# Distro_schematic.net
KiCad netlist of a schematic drawn in Altium Designer
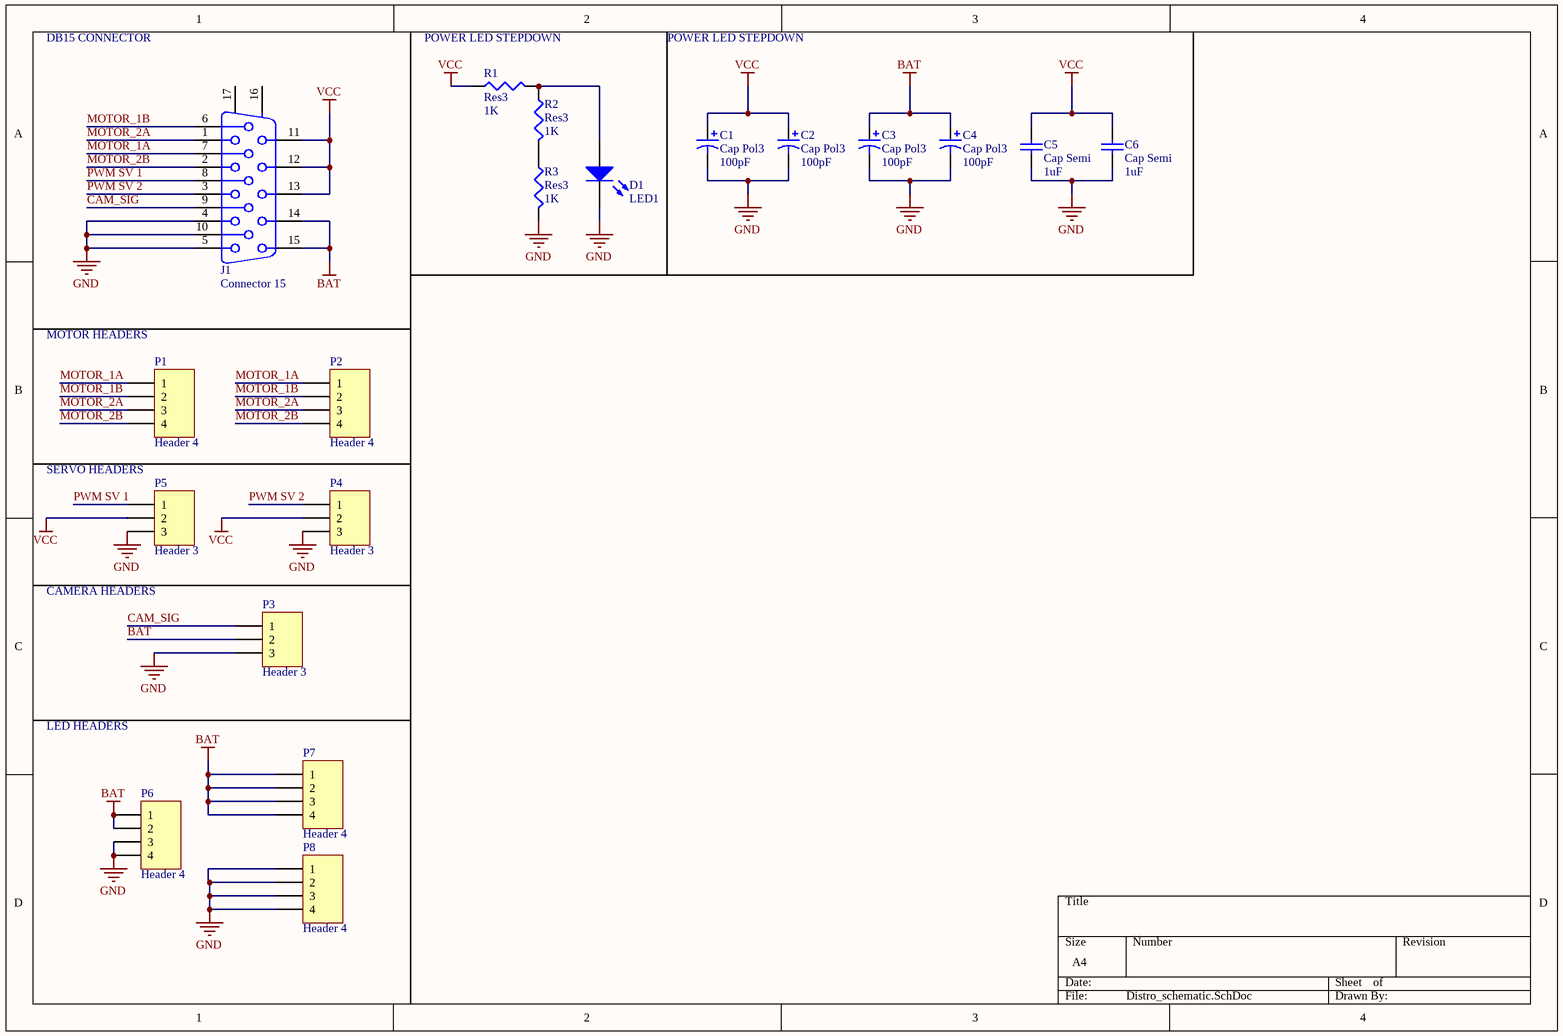
[diagram p0: Distro_schematic.SchDoc]

(export (version "E")
  (design (tool "Eeschema 10.0.6"))
  (components
    (comp (ref "C1")
      (value "Cap Pol3")
      (footprint "C0805")
      (description "Polarized Capacitor (Surface Mount)")
      (fields (field (name "ALTIUM_VALUE") "100pF") (field (name "PUBLISHER") "Altium Limited"))
      (libsource (lib "Miscellaneous Devices") (part "Cap Pol3"))
    )
    (comp (ref "C2")
      (value "Cap Pol3")
      (footprint "C0805")
      (description "Polarized Capacitor (Surface Mount)")
      (fields (field (name "ALTIUM_VALUE") "100pF") (field (name "PUBLISHER") "Altium Limited"))
      (libsource (lib "Miscellaneous Devices") (part "Cap Pol3"))
    )
    (comp (ref "C3")
      (value "Cap Pol3")
      (footprint "C0805")
      (description "Polarized Capacitor (Surface Mount)")
      (fields (field (name "ALTIUM_VALUE") "100pF") (field (name "PUBLISHER") "Altium Limited"))
      (libsource (lib "Miscellaneous Devices") (part "Cap Pol3"))
    )
    (comp (ref "C4")
      (value "Cap Pol3")
      (footprint "C0805")
      (description "Polarized Capacitor (Surface Mount)")
      (fields (field (name "ALTIUM_VALUE") "100pF") (field (name "PUBLISHER") "Altium Limited"))
      (libsource (lib "Miscellaneous Devices") (part "Cap Pol3"))
    )
    (comp (ref "C5")
      (value "Cap Semi")
      (footprint "C1206")
      (description "Capacitor (Semiconductor SIM Model)")
      (fields (field (name "ALTIUM_VALUE") "1uF") (field (name "PUBLISHER") "Altium Limited"))
      (libsource (lib "Miscellaneous Devices") (part "Cap Semi"))
    )
    (comp (ref "C6")
      (value "Cap Semi")
      (footprint "C1206")
      (description "Capacitor (Semiconductor SIM Model)")
      (fields (field (name "ALTIUM_VALUE") "1uF") (field (name "PUBLISHER") "Altium Limited"))
      (libsource (lib "Miscellaneous Devices") (part "Cap Semi"))
    )
    (comp (ref "D1")
      (value "LED1")
      (footprint "L0603")
      (description "Typical RED GaAs LED")
      (fields (field (name "PUBLISHER") "Altium Limited"))
      (libsource (lib "Miscellaneous Devices") (part "LED1"))
    )
    (comp (ref "J1")
      (value "Connector 15")
      (footprint "VGA_F:PCBComponent_1")
      (description "Receptacle Assembly, 15-Pin, Sim Line Connector")
      (fields (field (name "PUBLISHER") "Altium Limited"))
      (libsource (lib "Miscellaneous Connectors") (part "Connector 15"))
    )
    (comp (ref "P1")
      (value "Header 4")
      (footprint "HDR1X4")
      (description "Header, 4-Pin")
      (fields (field (name "PUBLISHER") "Altium Limited"))
      (libsource (lib "Miscellaneous Connectors") (part "Header 4"))
    )
    (comp (ref "P2")
      (value "Header 4")
      (footprint "HDR1X4")
      (description "Header, 4-Pin")
      (fields (field (name "PUBLISHER") "Altium Limited"))
      (libsource (lib "Miscellaneous Connectors") (part "Header 4"))
    )
    (comp (ref "P3")
      (value "Header 3")
      (footprint "HDR1X3")
      (description "Header, 3-Pin")
      (fields (field (name "PUBLISHER") "Altium Limited"))
      (libsource (lib "Miscellaneous Connectors") (part "Header 3"))
    )
    (comp (ref "P4")
      (value "Header 3")
      (footprint "HDR1X3")
      (description "Header, 3-Pin")
      (fields (field (name "PUBLISHER") "Altium Limited"))
      (libsource (lib "Miscellaneous Connectors") (part "Header 3"))
    )
    (comp (ref "P5")
      (value "Header 3")
      (footprint "HDR1X3")
      (description "Header, 3-Pin")
      (fields (field (name "PUBLISHER") "Altium Limited"))
      (libsource (lib "Miscellaneous Connectors") (part "Header 3"))
    )
    (comp (ref "P6")
      (value "Header 4")
      (footprint "HDR1X4")
      (description "Header, 4-Pin")
      (fields (field (name "PUBLISHER") "Altium Limited"))
      (libsource (lib "Miscellaneous Connectors") (part "Header 4"))
    )
    (comp (ref "P7")
      (value "Header 4")
      (footprint "HDR1X4")
      (description "Header, 4-Pin")
      (fields (field (name "PUBLISHER") "Altium Limited"))
      (libsource (lib "Miscellaneous Connectors") (part "Header 4"))
    )
    (comp (ref "P8")
      (value "Header 4")
      (footprint "HDR1X4")
      (description "Header, 4-Pin")
      (fields (field (name "PUBLISHER") "Altium Limited"))
      (libsource (lib "Miscellaneous Connectors") (part "Header 4"))
    )
    (comp (ref "R1")
      (value "Res3")
      (footprint "J1-0603")
      (description "Resistor")
      (fields (field (name "ALTIUM_VALUE") "1K") (field (name "PUBLISHER") "Altium Limited"))
      (libsource (lib "Miscellaneous Devices") (part "Res3"))
    )
    (comp (ref "R2")
      (value "Res3")
      (footprint "J1-0603")
      (description "Resistor")
      (fields (field (name "ALTIUM_VALUE") "1K") (field (name "PUBLISHER") "Altium Limited"))
      (libsource (lib "Miscellaneous Devices") (part "Res3"))
    )
    (comp (ref "R3")
      (value "Res3")
      (footprint "J1-0603")
      (description "Resistor")
      (fields (field (name "ALTIUM_VALUE") "1K") (field (name "PUBLISHER") "Altium Limited"))
      (libsource (lib "Miscellaneous Devices") (part "Res3"))
    )
  )
  (nets
    (net (code "1") (name "/CAM_SIG") (class "Default")
      (node (ref "J1") (pin "9") (pinfunction "9_9") (pintype "passive"))
      (node (ref "P3") (pin "1") (pinfunction "1_1") (pintype "passive"))
    )
    (net (code "2") (name "/MOTOR_1A") (class "Default")
      (node (ref "J1") (pin "7") (pinfunction "7_7") (pintype "passive"))
      (node (ref "P1") (pin "1") (pinfunction "1_1") (pintype "passive"))
      (node (ref "P2") (pin "1") (pinfunction "1_1") (pintype "passive"))
    )
    (net (code "3") (name "/MOTOR_1B") (class "Default")
      (node (ref "J1") (pin "6") (pinfunction "6_6") (pintype "passive"))
      (node (ref "P1") (pin "2") (pinfunction "2_2") (pintype "passive"))
      (node (ref "P2") (pin "2") (pinfunction "2_2") (pintype "passive"))
    )
    (net (code "4") (name "/MOTOR_2A") (class "Default")
      (node (ref "J1") (pin "1") (pinfunction "1_1") (pintype "passive"))
      (node (ref "P1") (pin "3") (pinfunction "3_3") (pintype "passive"))
      (node (ref "P2") (pin "3") (pinfunction "3_3") (pintype "passive"))
    )
    (net (code "5") (name "/MOTOR_2B") (class "Default")
      (node (ref "J1") (pin "2") (pinfunction "2_2") (pintype "passive"))
      (node (ref "P1") (pin "4") (pinfunction "4_4") (pintype "passive"))
      (node (ref "P2") (pin "4") (pinfunction "4_4") (pintype "passive"))
    )
    (net (code "6") (name "/PWM SV 1") (class "Default")
      (node (ref "J1") (pin "8") (pinfunction "8_8") (pintype "passive"))
      (node (ref "P5") (pin "1") (pinfunction "1_1") (pintype "passive"))
    )
    (net (code "7") (name "/PWM SV 2") (class "Default")
      (node (ref "J1") (pin "3") (pinfunction "3_3") (pintype "passive"))
      (node (ref "P4") (pin "1") (pinfunction "1_1") (pintype "passive"))
    )
    (net (code "8") (name "BAT") (class "Default")
      (node (ref "C3") (pin "1") (pinfunction "1_1") (pintype "passive"))
      (node (ref "C4") (pin "1") (pinfunction "1_1") (pintype "passive"))
      (node (ref "J1") (pin "14") (pinfunction "14_14") (pintype "passive"))
      (node (ref "J1") (pin "15") (pinfunction "15_15") (pintype "passive"))
      (node (ref "P3") (pin "2") (pinfunction "2_2") (pintype "passive"))
      (node (ref "P6") (pin "1") (pinfunction "1_1") (pintype "passive"))
      (node (ref "P6") (pin "2") (pinfunction "2_2") (pintype "passive"))
      (node (ref "P7") (pin "1") (pinfunction "1_1") (pintype "passive"))
      (node (ref "P7") (pin "2") (pinfunction "2_2") (pintype "passive"))
      (node (ref "P7") (pin "3") (pinfunction "3_3") (pintype "passive"))
      (node (ref "P7") (pin "4") (pinfunction "4_4") (pintype "passive"))
    )
    (net (code "9") (name "GND") (class "Default")
      (node (ref "C1") (pin "2") (pinfunction "2_2") (pintype "passive"))
      (node (ref "C2") (pin "2") (pinfunction "2_2") (pintype "passive"))
      (node (ref "C3") (pin "2") (pinfunction "2_2") (pintype "passive"))
      (node (ref "C4") (pin "2") (pinfunction "2_2") (pintype "passive"))
      (node (ref "C5") (pin "1") (pinfunction "1_1") (pintype "passive"))
      (node (ref "C6") (pin "1") (pinfunction "1_1") (pintype "passive"))
      (node (ref "D1") (pin "2") (pinfunction "K_2") (pintype "passive"))
      (node (ref "J1") (pin "10") (pinfunction "10_10") (pintype "passive"))
      (node (ref "J1") (pin "4") (pinfunction "4_4") (pintype "passive"))
      (node (ref "J1") (pin "5") (pinfunction "5_5") (pintype "passive"))
      (node (ref "P3") (pin "3") (pinfunction "3_3") (pintype "passive"))
      (node (ref "P4") (pin "3") (pinfunction "3_3") (pintype "passive"))
      (node (ref "P5") (pin "3") (pinfunction "3_3") (pintype "passive"))
      (node (ref "P6") (pin "3") (pinfunction "3_3") (pintype "passive"))
      (node (ref "P6") (pin "4") (pinfunction "4_4") (pintype "passive"))
      (node (ref "P8") (pin "1") (pinfunction "1_1") (pintype "passive"))
      (node (ref "P8") (pin "2") (pinfunction "2_2") (pintype "passive"))
      (node (ref "P8") (pin "3") (pinfunction "3_3") (pintype "passive"))
      (node (ref "P8") (pin "4") (pinfunction "4_4") (pintype "passive"))
      (node (ref "R3") (pin "2") (pinfunction "2_2") (pintype "passive"))
    )
    (net (code "10") (name "Net-(D1-A)") (class "Default")
      (node (ref "D1") (pin "1") (pinfunction "A_1") (pintype "passive"))
      (node (ref "R1") (pin "2") (pinfunction "2_2") (pintype "passive"))
      (node (ref "R2") (pin "1") (pinfunction "1_1") (pintype "passive"))
    )
    (net (code "11") (name "Net-(R2-Pad2)") (class "Default")
      (node (ref "R2") (pin "2") (pinfunction "2_2") (pintype "passive"))
      (node (ref "R3") (pin "1") (pinfunction "1_1") (pintype "passive"))
    )
    (net (code "12") (name "VCC") (class "Default")
      (node (ref "C1") (pin "1") (pinfunction "1_1") (pintype "passive"))
      (node (ref "C2") (pin "1") (pinfunction "1_1") (pintype "passive"))
      (node (ref "C5") (pin "2") (pinfunction "2_2") (pintype "passive"))
      (node (ref "C6") (pin "2") (pinfunction "2_2") (pintype "passive"))
      (node (ref "J1") (pin "11") (pinfunction "11_11") (pintype "passive"))
      (node (ref "J1") (pin "12") (pinfunction "12_12") (pintype "passive"))
      (node (ref "J1") (pin "13") (pinfunction "13_13") (pintype "passive"))
      (node (ref "P4") (pin "2") (pinfunction "2_2") (pintype "passive"))
      (node (ref "P5") (pin "2") (pinfunction "2_2") (pintype "passive"))
      (node (ref "R1") (pin "1") (pinfunction "1_1") (pintype "passive"))
    )
    (net (code "13") (name "unconnected-(J1-MH1-Pad16)") (class "Default")
      (node (ref "J1") (pin "16") (pinfunction "MH1_16") (pintype "passive"))
    )
    (net (code "14") (name "unconnected-(J1-MH2-Pad17)") (class "Default")
      (node (ref "J1") (pin "17") (pinfunction "MH2_17") (pintype "passive"))
    )
  )
)
